# LEDSlave.net
KiCad netlist of a schematic drawn in EAGLE
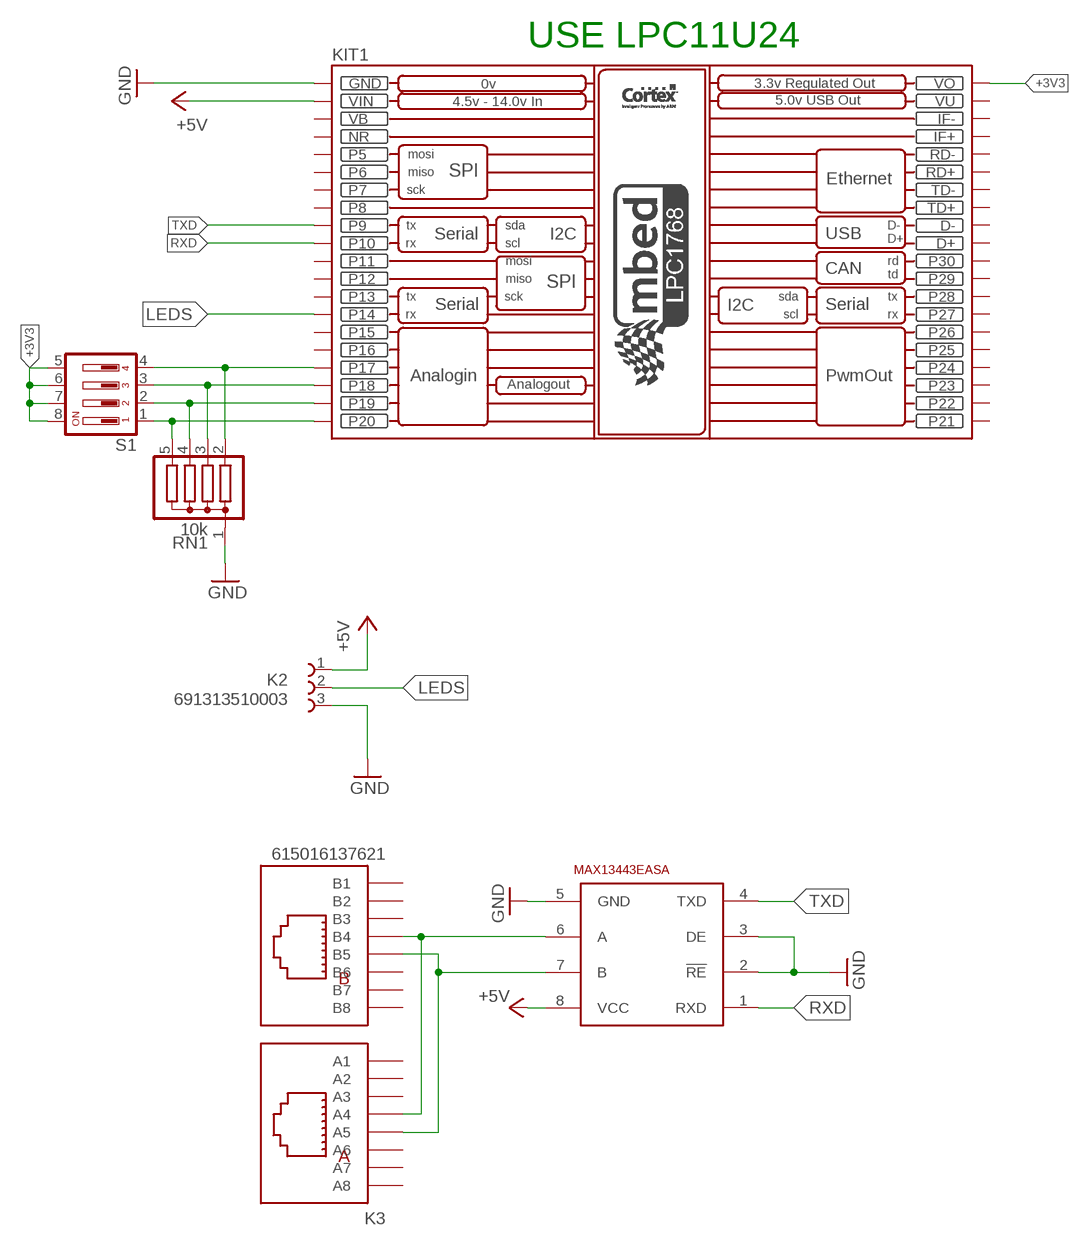
[diagram p0: schematic, sheet 1]

(export (version "E")
  (design (tool "Eeschema 10.0.6"))
  (components
    (comp (ref "K2")
      (value "691313510003")
      (footprint "eagle-import:691313510003")
      (libsource (lib "eagle-import") (part "691313510003"))
    )
    (comp (ref "K3")
      (value "615016137621")
      (footprint "eagle-import:615016137621")
      (libsource (lib "eagle-import") (part "615016137621"))
    )
    (comp (ref "KIT1")
      (value "MBED_NXP_LPC1768")
      (footprint "eagle-import:MBED-KIT")
      (libsource (lib "eagle-import") (part "MBED_NXP_LPC1768"))
    )
    (comp (ref "RN1")
      (value "10k")
      (footprint "eagle-import:SIL5")
      (libsource (lib "eagle-import") (part "G04R"))
    )
    (comp (ref "S1")
      (value "DA04")
      (footprint "eagle-import:DA-04")
      (fields (field (name "MPN") "MCDA04"))
      (libsource (lib "eagle-import") (part "DA04"))
    )
    (comp (ref "U$1")
      (value "MAX13443EASA")
      (footprint "eagle-import:SO08")
      (libsource (lib "eagle-import") (part "MAX13443EASA"))
    )
  )
  (nets
    (net (code "1") (name "+3V3") (class "Default")
      (node (ref "KIT1") (pin "VOUT") (pinfunction "VO_VOUT") (pintype "power_in"))
      (node (ref "S1") (pin "5") (pinfunction "5_5") (pintype "passive"))
      (node (ref "S1") (pin "6") (pinfunction "6_6") (pintype "passive"))
      (node (ref "S1") (pin "7") (pinfunction "7_7") (pintype "passive"))
      (node (ref "S1") (pin "8") (pinfunction "8_8") (pintype "passive"))
    )
    (net (code "2") (name "+5V") (class "Default")
      (node (ref "K2") (pin "1") (pinfunction "1_1") (pintype "passive"))
      (node (ref "KIT1") (pin "VIN") (pinfunction "VIN_VIN") (pintype "power_in"))
      (node (ref "U$1") (pin "8") (pinfunction "VCC_8") (pintype "bidirectional"))
    )
    (net (code "3") (name "/NR") (class "Default")
      (node (ref "KIT1") (pin "NR") (pinfunction "NR_NR") (pintype "power_in"))
    )
    (net (code "4") (name "/VB") (class "Default")
      (node (ref "KIT1") (pin "VB") (pinfunction "VB_VB") (pintype "power_in"))
    )
    (net (code "5") (name "/VU") (class "Default")
      (node (ref "KIT1") (pin "VU") (pinfunction "VU_VU") (pintype "power_in"))
    )
    (net (code "6") (name "GND") (class "Default")
      (node (ref "K2") (pin "3") (pinfunction "3_3") (pintype "passive"))
      (node (ref "KIT1") (pin "GND") (pinfunction "GND_GND") (pintype "power_in"))
      (node (ref "RN1") (pin "1") (pinfunction "1_1") (pintype "passive"))
      (node (ref "U$1") (pin "2") (pinfunction "~{RE}_2") (pintype "bidirectional"))
      (node (ref "U$1") (pin "3") (pinfunction "DE_3") (pintype "bidirectional"))
      (node (ref "U$1") (pin "5") (pinfunction "GND_5") (pintype "bidirectional"))
    )
    (net (code "7") (name "LEDS") (class "Default")
      (node (ref "K2") (pin "2") (pinfunction "2_2") (pintype "passive"))
      (node (ref "KIT1") (pin "P$14") (pinfunction "P14_P$14") (pintype "bidirectional"))
    )
    (net (code "8") (name "Net-(KIT1-P17)") (class "Default")
      (node (ref "KIT1") (pin "P$17") (pinfunction "P17_P$17") (pintype "bidirectional"))
      (node (ref "RN1") (pin "2") (pinfunction "2_2") (pintype "passive"))
      (node (ref "S1") (pin "4") (pinfunction "4_4") (pintype "passive"))
    )
    (net (code "9") (name "Net-(KIT1-P18)") (class "Default")
      (node (ref "KIT1") (pin "P$18") (pinfunction "P18_P$18") (pintype "bidirectional"))
      (node (ref "RN1") (pin "3") (pinfunction "3_3") (pintype "passive"))
      (node (ref "S1") (pin "3") (pinfunction "3_3") (pintype "passive"))
    )
    (net (code "10") (name "Net-(KIT1-P19)") (class "Default")
      (node (ref "KIT1") (pin "P$19") (pinfunction "P19_P$19") (pintype "bidirectional"))
      (node (ref "RN1") (pin "4") (pinfunction "4_4") (pintype "passive"))
      (node (ref "S1") (pin "2") (pinfunction "2_2") (pintype "passive"))
    )
    (net (code "11") (name "Net-(KIT1-P20)") (class "Default")
      (node (ref "KIT1") (pin "P$20") (pinfunction "P20_P$20") (pintype "bidirectional"))
      (node (ref "RN1") (pin "5") (pinfunction "5_5") (pintype "passive"))
      (node (ref "S1") (pin "1") (pinfunction "1_1") (pintype "passive"))
    )
    (net (code "12") (name "Net-(U$1-A)") (class "Default")
      (node (ref "K3") (pin "A4") (pinfunction "A4_A4") (pintype "passive"))
      (node (ref "K3") (pin "B4") (pinfunction "B4_B4") (pintype "passive"))
      (node (ref "U$1") (pin "6") (pinfunction "A_6") (pintype "bidirectional"))
    )
    (net (code "13") (name "Net-(U$1-B)") (class "Default")
      (node (ref "K3") (pin "A5") (pinfunction "A5_A5") (pintype "passive"))
      (node (ref "K3") (pin "B5") (pinfunction "B5_B5") (pintype "passive"))
      (node (ref "U$1") (pin "7") (pinfunction "B_7") (pintype "bidirectional"))
    )
    (net (code "14") (name "RXD") (class "Default")
      (node (ref "KIT1") (pin "P$10") (pinfunction "P10_P$10") (pintype "bidirectional"))
      (node (ref "U$1") (pin "1") (pinfunction "RXD_1") (pintype "bidirectional"))
    )
    (net (code "15") (name "TXD") (class "Default")
      (node (ref "KIT1") (pin "P$9") (pinfunction "P9_P$9") (pintype "bidirectional"))
      (node (ref "U$1") (pin "4") (pinfunction "TXD_4") (pintype "bidirectional"))
    )
    (net (code "16") (name "unconnected-(K3-PadA1)") (class "Default")
      (node (ref "K3") (pin "A1") (pinfunction "A1_A1") (pintype "passive"))
    )
    (net (code "17") (name "unconnected-(K3-PadA2)") (class "Default")
      (node (ref "K3") (pin "A2") (pinfunction "A2_A2") (pintype "passive"))
    )
    (net (code "18") (name "unconnected-(K3-PadA3)") (class "Default")
      (node (ref "K3") (pin "A3") (pinfunction "A3_A3") (pintype "passive"))
    )
    (net (code "19") (name "unconnected-(K3-PadA6)") (class "Default")
      (node (ref "K3") (pin "A6") (pinfunction "A6_A6") (pintype "passive"))
    )
    (net (code "20") (name "unconnected-(K3-PadA7)") (class "Default")
      (node (ref "K3") (pin "A7") (pinfunction "A7_A7") (pintype "passive"))
    )
    (net (code "21") (name "unconnected-(K3-PadA8)") (class "Default")
      (node (ref "K3") (pin "A8") (pinfunction "A8_A8") (pintype "passive"))
    )
    (net (code "22") (name "unconnected-(K3-PadB1)") (class "Default")
      (node (ref "K3") (pin "B1") (pinfunction "B1_B1") (pintype "passive"))
    )
    (net (code "23") (name "unconnected-(K3-PadB2)") (class "Default")
      (node (ref "K3") (pin "B2") (pinfunction "B2_B2") (pintype "passive"))
    )
    (net (code "24") (name "unconnected-(K3-PadB3)") (class "Default")
      (node (ref "K3") (pin "B3") (pinfunction "B3_B3") (pintype "passive"))
    )
    (net (code "25") (name "unconnected-(K3-PadB6)") (class "Default")
      (node (ref "K3") (pin "B6") (pinfunction "B6_B6") (pintype "passive"))
    )
    (net (code "26") (name "unconnected-(K3-PadB7)") (class "Default")
      (node (ref "K3") (pin "B7") (pinfunction "B7_B7") (pintype "passive"))
    )
    (net (code "27") (name "unconnected-(K3-PadB8)") (class "Default")
      (node (ref "K3") (pin "B8") (pinfunction "B8_B8") (pintype "passive"))
    )
    (net (code "28") (name "unconnected-(KIT1-P5-PadP$5)") (class "Default")
      (node (ref "KIT1") (pin "P$5") (pinfunction "P5_P$5") (pintype "bidirectional"))
    )
    (net (code "29") (name "unconnected-(KIT1-P6-PadP$6)") (class "Default")
      (node (ref "KIT1") (pin "P$6") (pinfunction "P6_P$6") (pintype "bidirectional"))
    )
    (net (code "30") (name "unconnected-(KIT1-P7-PadP$7)") (class "Default")
      (node (ref "KIT1") (pin "P$7") (pinfunction "P7_P$7") (pintype "bidirectional"))
    )
    (net (code "31") (name "unconnected-(KIT1-P8-PadP$8)") (class "Default")
      (node (ref "KIT1") (pin "P$8") (pinfunction "P8_P$8") (pintype "bidirectional"))
    )
    (net (code "32") (name "unconnected-(KIT1-P11-PadP$11)") (class "Default")
      (node (ref "KIT1") (pin "P$11") (pinfunction "P11_P$11") (pintype "bidirectional"))
    )
    (net (code "33") (name "unconnected-(KIT1-P12-PadP$12)") (class "Default")
      (node (ref "KIT1") (pin "P$12") (pinfunction "P12_P$12") (pintype "bidirectional"))
    )
    (net (code "34") (name "unconnected-(KIT1-P13-PadP$13)") (class "Default")
      (node (ref "KIT1") (pin "P$13") (pinfunction "P13_P$13") (pintype "bidirectional"))
    )
    (net (code "35") (name "unconnected-(KIT1-P15-PadP$15)") (class "Default")
      (node (ref "KIT1") (pin "P$15") (pinfunction "P15_P$15") (pintype "bidirectional"))
    )
    (net (code "36") (name "unconnected-(KIT1-P16-PadP$16)") (class "Default")
      (node (ref "KIT1") (pin "P$16") (pinfunction "P16_P$16") (pintype "bidirectional"))
    )
    (net (code "37") (name "unconnected-(KIT1-P21-PadP$21)") (class "Default")
      (node (ref "KIT1") (pin "P$21") (pinfunction "P21_P$21") (pintype "bidirectional"))
    )
    (net (code "38") (name "unconnected-(KIT1-P22-PadP$22)") (class "Default")
      (node (ref "KIT1") (pin "P$22") (pinfunction "P22_P$22") (pintype "bidirectional"))
    )
    (net (code "39") (name "unconnected-(KIT1-P23-PadP$23)") (class "Default")
      (node (ref "KIT1") (pin "P$23") (pinfunction "P23_P$23") (pintype "bidirectional"))
    )
    (net (code "40") (name "unconnected-(KIT1-P24-PadP$24)") (class "Default")
      (node (ref "KIT1") (pin "P$24") (pinfunction "P24_P$24") (pintype "bidirectional"))
    )
    (net (code "41") (name "unconnected-(KIT1-P25-PadP$25)") (class "Default")
      (node (ref "KIT1") (pin "P$25") (pinfunction "P25_P$25") (pintype "bidirectional"))
    )
    (net (code "42") (name "unconnected-(KIT1-P26-PadP$26)") (class "Default")
      (node (ref "KIT1") (pin "P$26") (pinfunction "P26_P$26") (pintype "bidirectional"))
    )
    (net (code "43") (name "unconnected-(KIT1-P27-PadP$27)") (class "Default")
      (node (ref "KIT1") (pin "P$27") (pinfunction "P27_P$27") (pintype "bidirectional"))
    )
    (net (code "44") (name "unconnected-(KIT1-P28-PadP$28)") (class "Default")
      (node (ref "KIT1") (pin "P$28") (pinfunction "P28_P$28") (pintype "bidirectional"))
    )
    (net (code "45") (name "unconnected-(KIT1-P29-PadP$29)") (class "Default")
      (node (ref "KIT1") (pin "P$29") (pinfunction "P29_P$29") (pintype "bidirectional"))
    )
    (net (code "46") (name "unconnected-(KIT1-P30-PadP$30)") (class "Default")
      (node (ref "KIT1") (pin "P$30") (pinfunction "P30_P$30") (pintype "bidirectional"))
    )
    (net (code "47") (name "unconnected-(KIT1-PadD+)") (class "Default")
      (node (ref "KIT1") (pin "D+") (pinfunction "D+_D+") (pintype "bidirectional"))
    )
    (net (code "48") (name "unconnected-(KIT1-PadD-)") (class "Default")
      (node (ref "KIT1") (pin "D-") (pinfunction "D-_D-") (pintype "bidirectional"))
    )
    (net (code "49") (name "unconnected-(KIT1-PadIF+)") (class "Default")
      (node (ref "KIT1") (pin "IF+") (pinfunction "IF+_IF+") (pintype "bidirectional"))
    )
    (net (code "50") (name "unconnected-(KIT1-PadIF-)") (class "Default")
      (node (ref "KIT1") (pin "IF-") (pinfunction "IF-_IF-") (pintype "bidirectional"))
    )
    (net (code "51") (name "unconnected-(KIT1-PadRD+)") (class "Default")
      (node (ref "KIT1") (pin "RD+") (pinfunction "RD+_RD+") (pintype "bidirectional"))
    )
    (net (code "52") (name "unconnected-(KIT1-PadRD-)") (class "Default")
      (node (ref "KIT1") (pin "RD-") (pinfunction "RD-_RD-") (pintype "bidirectional"))
    )
    (net (code "53") (name "unconnected-(KIT1-PadTD+)") (class "Default")
      (node (ref "KIT1") (pin "TD+") (pinfunction "TD+_TD+") (pintype "bidirectional"))
    )
    (net (code "54") (name "unconnected-(KIT1-PadTD-)") (class "Default")
      (node (ref "KIT1") (pin "TD-") (pinfunction "TD-_TD-") (pintype "bidirectional"))
    )
  )
)
